# 07_FMC_LPC_Interface.net
KiCad netlist of a schematic drawn in Altium Designer
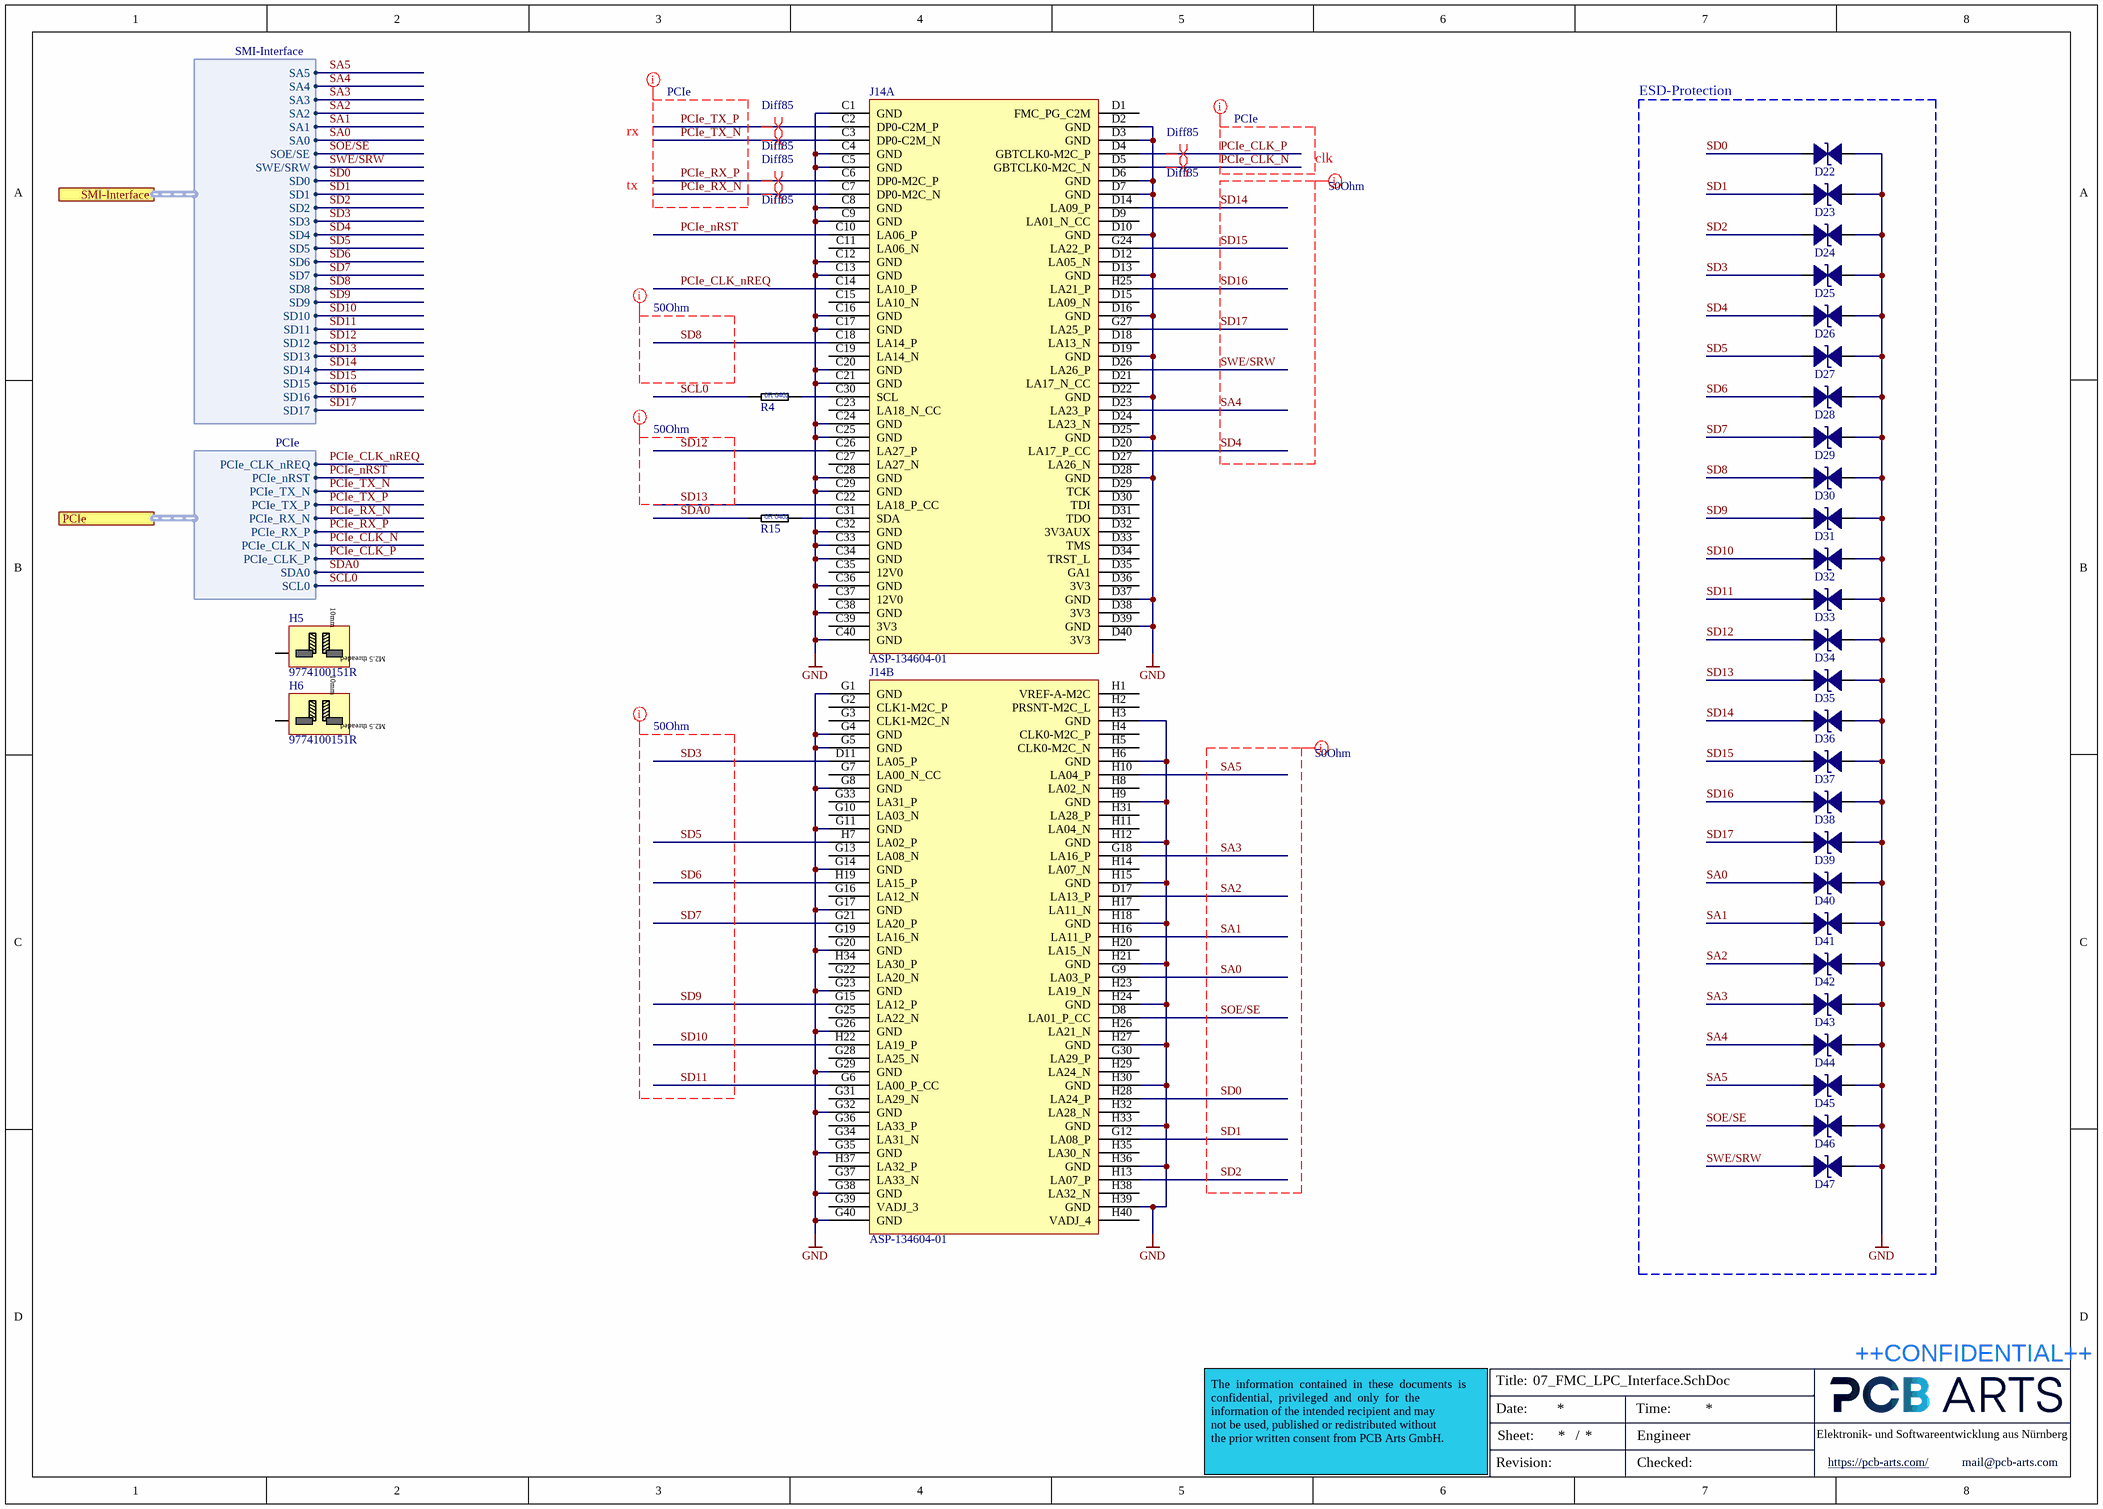
[diagram p0: 07_FMC_LPC_Interface.SchDoc]

(export (version "E")
  (design (tool "Eeschema 10.0.6"))
  (components
    (comp (ref "D22")
      (value "CESDP0402UC5VB")
      (footprint "Protec:TVS_0402")
      (description "Low Capacitance ESD Protection Diode 0402")
      (libsource (lib "Protec") (part "CESDP0402UC5VB_TVS Diode 0402"))
    )
    (comp (ref "D23")
      (value "CESDP0402UC5VB")
      (footprint "Protec:TVS_0402")
      (description "Low Capacitance ESD Protection Diode 0402")
      (libsource (lib "Protec") (part "CESDP0402UC5VB_TVS Diode 0402"))
    )
    (comp (ref "D24")
      (value "CESDP0402UC5VB")
      (footprint "Protec:TVS_0402")
      (description "Low Capacitance ESD Protection Diode 0402")
      (libsource (lib "Protec") (part "CESDP0402UC5VB_TVS Diode 0402"))
    )
    (comp (ref "D25")
      (value "CESDP0402UC5VB")
      (footprint "Protec:TVS_0402")
      (description "Low Capacitance ESD Protection Diode 0402")
      (libsource (lib "Protec") (part "CESDP0402UC5VB_TVS Diode 0402"))
    )
    (comp (ref "D26")
      (value "CESDP0402UC5VB")
      (footprint "Protec:TVS_0402")
      (description "Low Capacitance ESD Protection Diode 0402")
      (libsource (lib "Protec") (part "CESDP0402UC5VB_TVS Diode 0402"))
    )
    (comp (ref "D27")
      (value "CESDP0402UC5VB")
      (footprint "Protec:TVS_0402")
      (description "Low Capacitance ESD Protection Diode 0402")
      (libsource (lib "Protec") (part "CESDP0402UC5VB_TVS Diode 0402"))
    )
    (comp (ref "D28")
      (value "CESDP0402UC5VB")
      (footprint "Protec:TVS_0402")
      (description "Low Capacitance ESD Protection Diode 0402")
      (libsource (lib "Protec") (part "CESDP0402UC5VB_TVS Diode 0402"))
    )
    (comp (ref "D29")
      (value "CESDP0402UC5VB")
      (footprint "Protec:TVS_0402")
      (description "Low Capacitance ESD Protection Diode 0402")
      (libsource (lib "Protec") (part "CESDP0402UC5VB_TVS Diode 0402"))
    )
    (comp (ref "D30")
      (value "CESDP0402UC5VB")
      (footprint "Protec:TVS_0402")
      (description "Low Capacitance ESD Protection Diode 0402")
      (libsource (lib "Protec") (part "CESDP0402UC5VB_TVS Diode 0402"))
    )
    (comp (ref "D31")
      (value "CESDP0402UC5VB")
      (footprint "Protec:TVS_0402")
      (description "Low Capacitance ESD Protection Diode 0402")
      (libsource (lib "Protec") (part "CESDP0402UC5VB_TVS Diode 0402"))
    )
    (comp (ref "D32")
      (value "CESDP0402UC5VB")
      (footprint "Protec:TVS_0402")
      (description "Low Capacitance ESD Protection Diode 0402")
      (libsource (lib "Protec") (part "CESDP0402UC5VB_TVS Diode 0402"))
    )
    (comp (ref "D33")
      (value "CESDP0402UC5VB")
      (footprint "Protec:TVS_0402")
      (description "Low Capacitance ESD Protection Diode 0402")
      (libsource (lib "Protec") (part "CESDP0402UC5VB_TVS Diode 0402"))
    )
    (comp (ref "D34")
      (value "CESDP0402UC5VB")
      (footprint "Protec:TVS_0402")
      (description "Low Capacitance ESD Protection Diode 0402")
      (libsource (lib "Protec") (part "CESDP0402UC5VB_TVS Diode 0402"))
    )
    (comp (ref "D35")
      (value "CESDP0402UC5VB")
      (footprint "Protec:TVS_0402")
      (description "Low Capacitance ESD Protection Diode 0402")
      (libsource (lib "Protec") (part "CESDP0402UC5VB_TVS Diode 0402"))
    )
    (comp (ref "D36")
      (value "CESDP0402UC5VB")
      (footprint "Protec:TVS_0402")
      (description "Low Capacitance ESD Protection Diode 0402")
      (libsource (lib "Protec") (part "CESDP0402UC5VB_TVS Diode 0402"))
    )
    (comp (ref "D37")
      (value "CESDP0402UC5VB")
      (footprint "Protec:TVS_0402")
      (description "Low Capacitance ESD Protection Diode 0402")
      (libsource (lib "Protec") (part "CESDP0402UC5VB_TVS Diode 0402"))
    )
    (comp (ref "D38")
      (value "CESDP0402UC5VB")
      (footprint "Protec:TVS_0402")
      (description "Low Capacitance ESD Protection Diode 0402")
      (libsource (lib "Protec") (part "CESDP0402UC5VB_TVS Diode 0402"))
    )
    (comp (ref "D39")
      (value "CESDP0402UC5VB")
      (footprint "Protec:TVS_0402")
      (description "Low Capacitance ESD Protection Diode 0402")
      (libsource (lib "Protec") (part "CESDP0402UC5VB_TVS Diode 0402"))
    )
    (comp (ref "D40")
      (value "CESDP0402UC5VB")
      (footprint "Protec:TVS_0402")
      (description "Low Capacitance ESD Protection Diode 0402")
      (libsource (lib "Protec") (part "CESDP0402UC5VB_TVS Diode 0402"))
    )
    (comp (ref "D41")
      (value "CESDP0402UC5VB")
      (footprint "Protec:TVS_0402")
      (description "Low Capacitance ESD Protection Diode 0402")
      (libsource (lib "Protec") (part "CESDP0402UC5VB_TVS Diode 0402"))
    )
    (comp (ref "D42")
      (value "CESDP0402UC5VB")
      (footprint "Protec:TVS_0402")
      (description "Low Capacitance ESD Protection Diode 0402")
      (libsource (lib "Protec") (part "CESDP0402UC5VB_TVS Diode 0402"))
    )
    (comp (ref "D43")
      (value "CESDP0402UC5VB")
      (footprint "Protec:TVS_0402")
      (description "Low Capacitance ESD Protection Diode 0402")
      (libsource (lib "Protec") (part "CESDP0402UC5VB_TVS Diode 0402"))
    )
    (comp (ref "D44")
      (value "CESDP0402UC5VB")
      (footprint "Protec:TVS_0402")
      (description "Low Capacitance ESD Protection Diode 0402")
      (libsource (lib "Protec") (part "CESDP0402UC5VB_TVS Diode 0402"))
    )
    (comp (ref "D45")
      (value "CESDP0402UC5VB")
      (footprint "Protec:TVS_0402")
      (description "Low Capacitance ESD Protection Diode 0402")
      (libsource (lib "Protec") (part "CESDP0402UC5VB_TVS Diode 0402"))
    )
    (comp (ref "D46")
      (value "CESDP0402UC5VB")
      (footprint "Protec:TVS_0402")
      (description "Low Capacitance ESD Protection Diode 0402")
      (libsource (lib "Protec") (part "CESDP0402UC5VB_TVS Diode 0402"))
    )
    (comp (ref "D47")
      (value "CESDP0402UC5VB")
      (footprint "Protec:TVS_0402")
      (description "Low Capacitance ESD Protection Diode 0402")
      (libsource (lib "Protec") (part "CESDP0402UC5VB_TVS Diode 0402"))
    )
    (comp (ref "H5")
      (value "9774100151R")
      (footprint "Electro_Mech:9774100151R")
      (description "Würth Standoff M2.5 h:10mm 9774050151R")
      (libsource (lib "Electro_Mech") (part "Würth Standoff M2.5 h{colon}5mm_1"))
    )
    (comp (ref "H6")
      (value "9774100151R")
      (footprint "Electro_Mech:9774100151R")
      (description "Würth Standoff M2.5 h:10mm 9774050151R")
      (libsource (lib "Electro_Mech") (part "Würth Standoff M2.5 h{colon}5mm_1"))
    )
    (comp (ref "J14")
      (value "ASP-134604-01")
      (footprint "CONN:ASP-134604-01")
      (description "Female FMC-Connector mating plug")
      (libsource (lib "Conn") (part "ASP-134604-01_Female FMC-Connector mating plug"))
    )
    (comp (ref "R4")
      (value "0R Jumper")
      (footprint "res:RES_0402")
      (description "Thick Film Resistors - SMD 0Ohm")
      (libsource (lib "Res") (part "RES_0402_0R Jumper"))
    )
    (comp (ref "R15")
      (value "0R Jumper")
      (footprint "res:RES_0402")
      (description "Thick Film Resistors - SMD 0Ohm")
      (libsource (lib "Res") (part "RES_0402_0R Jumper"))
    )
  )
  (nets
    (net (code "3") (name "/PCIe_CLK_N") (class "Default")
      (node (ref "J14") (pin "D5") (pinfunction "GBTCLK0-M2C_N_D5") (pintype "passive"))
    )
    (net (code "4") (name "/PCIe_CLK_P") (class "Default")
      (node (ref "J14") (pin "D4") (pinfunction "GBTCLK0-M2C_P_D4") (pintype "passive"))
    )
    (net (code "5") (name "/PCIe_CLK_nREQ") (class "Default")
      (node (ref "J14") (pin "C14") (pinfunction "LA10_P_C14") (pintype "passive"))
    )
    (net (code "6") (name "/PCIe_RX_N") (class "Default")
      (node (ref "J14") (pin "C7") (pinfunction "DP0-M2C_N_C7") (pintype "passive"))
    )
    (net (code "7") (name "/PCIe_RX_P") (class "Default")
      (node (ref "J14") (pin "C6") (pinfunction "DP0-M2C_P_C6") (pintype "passive"))
    )
    (net (code "8") (name "/PCIe_TX_N") (class "Default")
      (node (ref "J14") (pin "C3") (pinfunction "DP0-C2M_N_C3") (pintype "passive"))
    )
    (net (code "9") (name "/PCIe_TX_P") (class "Default")
      (node (ref "J14") (pin "C2") (pinfunction "DP0-C2M_P_C2") (pintype "passive"))
    )
    (net (code "10") (name "/PCIe_nRST") (class "Default")
      (node (ref "J14") (pin "C10") (pinfunction "LA06_P_C10") (pintype "passive"))
    )
    (net (code "11") (name "/SA0") (class "Default")
      (node (ref "D40") (pin "1") (pinfunction "1_1") (pintype "passive"))
      (node (ref "J14") (pin "G9") (pinfunction "LA03_P_G9") (pintype "passive"))
    )
    (net (code "12") (name "/SA1") (class "Default")
      (node (ref "D41") (pin "1") (pinfunction "1_1") (pintype "passive"))
      (node (ref "J14") (pin "H16") (pinfunction "LA11_P_H16") (pintype "passive"))
    )
    (net (code "13") (name "/SA2") (class "Default")
      (node (ref "D42") (pin "1") (pinfunction "1_1") (pintype "passive"))
      (node (ref "J14") (pin "D17") (pinfunction "LA13_P_D17") (pintype "passive"))
    )
    (net (code "14") (name "/SA3") (class "Default")
      (node (ref "D43") (pin "1") (pinfunction "1_1") (pintype "passive"))
      (node (ref "J14") (pin "G18") (pinfunction "LA16_P_G18") (pintype "passive"))
    )
    (net (code "15") (name "/SA4") (class "Default")
      (node (ref "D44") (pin "1") (pinfunction "1_1") (pintype "passive"))
      (node (ref "J14") (pin "D23") (pinfunction "LA23_P_D23") (pintype "passive"))
    )
    (net (code "16") (name "/SA5") (class "Default")
      (node (ref "D45") (pin "1") (pinfunction "1_1") (pintype "passive"))
      (node (ref "J14") (pin "H10") (pinfunction "LA04_P_H10") (pintype "passive"))
    )
    (net (code "17") (name "/SCL0") (class "Default")
      (node (ref "R4") (pin "1") (pinfunction "1_1") (pintype "passive"))
    )
    (net (code "18") (name "/SD0") (class "Default")
      (node (ref "D22") (pin "1") (pinfunction "1_1") (pintype "passive"))
      (node (ref "J14") (pin "H28") (pinfunction "LA24_P_H28") (pintype "passive"))
    )
    (net (code "19") (name "/SD1") (class "Default")
      (node (ref "D23") (pin "1") (pinfunction "1_1") (pintype "passive"))
      (node (ref "J14") (pin "G12") (pinfunction "LA08_P_G12") (pintype "passive"))
    )
    (net (code "20") (name "/SD2") (class "Default")
      (node (ref "D24") (pin "1") (pinfunction "1_1") (pintype "passive"))
      (node (ref "J14") (pin "H13") (pinfunction "LA07_P_H13") (pintype "passive"))
    )
    (net (code "21") (name "/SD3") (class "Default")
      (node (ref "D25") (pin "1") (pinfunction "1_1") (pintype "passive"))
      (node (ref "J14") (pin "D11") (pinfunction "LA05_P_D11") (pintype "passive"))
    )
    (net (code "22") (name "/SD4") (class "Default")
      (node (ref "D26") (pin "1") (pinfunction "1_1") (pintype "passive"))
      (node (ref "J14") (pin "D20") (pinfunction "LA17_P_CC_D20") (pintype "passive"))
    )
    (net (code "23") (name "/SD5") (class "Default")
      (node (ref "D27") (pin "1") (pinfunction "1_1") (pintype "passive"))
      (node (ref "J14") (pin "H7") (pinfunction "LA02_P_H7") (pintype "passive"))
    )
    (net (code "24") (name "/SD6") (class "Default")
      (node (ref "D28") (pin "1") (pinfunction "1_1") (pintype "passive"))
      (node (ref "J14") (pin "H19") (pinfunction "LA15_P_H19") (pintype "passive"))
    )
    (net (code "25") (name "/SD7") (class "Default")
      (node (ref "D29") (pin "1") (pinfunction "1_1") (pintype "passive"))
      (node (ref "J14") (pin "G21") (pinfunction "LA20_P_G21") (pintype "passive"))
    )
    (net (code "26") (name "/SD8") (class "Default")
      (node (ref "D30") (pin "1") (pinfunction "1_1") (pintype "passive"))
      (node (ref "J14") (pin "C18") (pinfunction "LA14_P_C18") (pintype "passive"))
    )
    (net (code "27") (name "/SD9") (class "Default")
      (node (ref "D31") (pin "1") (pinfunction "1_1") (pintype "passive"))
      (node (ref "J14") (pin "G15") (pinfunction "LA12_P_G15") (pintype "passive"))
    )
    (net (code "28") (name "/SD10") (class "Default")
      (node (ref "D32") (pin "1") (pinfunction "1_1") (pintype "passive"))
      (node (ref "J14") (pin "H22") (pinfunction "LA19_P_H22") (pintype "passive"))
    )
    (net (code "29") (name "/SD11") (class "Default")
      (node (ref "D33") (pin "1") (pinfunction "1_1") (pintype "passive"))
      (node (ref "J14") (pin "G6") (pinfunction "LA00_P_CC_G6") (pintype "passive"))
    )
    (net (code "30") (name "/SD12") (class "Default")
      (node (ref "D34") (pin "1") (pinfunction "1_1") (pintype "passive"))
      (node (ref "J14") (pin "C26") (pinfunction "LA27_P_C26") (pintype "passive"))
    )
    (net (code "31") (name "/SD13") (class "Default")
      (node (ref "D35") (pin "1") (pinfunction "1_1") (pintype "passive"))
      (node (ref "J14") (pin "C22") (pinfunction "LA18_P_CC_C22") (pintype "passive"))
    )
    (net (code "32") (name "/SD14") (class "Default")
      (node (ref "D36") (pin "1") (pinfunction "1_1") (pintype "passive"))
      (node (ref "J14") (pin "D14") (pinfunction "LA09_P_D14") (pintype "passive"))
    )
    (net (code "33") (name "/SD15") (class "Default")
      (node (ref "D37") (pin "1") (pinfunction "1_1") (pintype "passive"))
      (node (ref "J14") (pin "G24") (pinfunction "LA22_P_G24") (pintype "passive"))
    )
    (net (code "34") (name "/SD16") (class "Default")
      (node (ref "D38") (pin "1") (pinfunction "1_1") (pintype "passive"))
      (node (ref "J14") (pin "H25") (pinfunction "LA21_P_H25") (pintype "passive"))
    )
    (net (code "35") (name "/SD17") (class "Default")
      (node (ref "D39") (pin "1") (pinfunction "1_1") (pintype "passive"))
      (node (ref "J14") (pin "G27") (pinfunction "LA25_P_G27") (pintype "passive"))
    )
    (net (code "36") (name "/SDA0") (class "Default")
      (node (ref "R15") (pin "1") (pinfunction "1_1") (pintype "passive"))
    )
    (net (code "37") (name "/SOE{slash}SE") (class "Default")
      (node (ref "D46") (pin "1") (pinfunction "1_1") (pintype "passive"))
      (node (ref "J14") (pin "D8") (pinfunction "LA01_P_CC_D8") (pintype "passive"))
    )
    (net (code "38") (name "/SWE{slash}SRW") (class "Default")
      (node (ref "D47") (pin "1") (pinfunction "1_1") (pintype "passive"))
      (node (ref "J14") (pin "D26") (pinfunction "LA26_P_D26") (pintype "passive"))
    )
    (net (code "41") (name "GND") (class "Default")
      (node (ref "D22") (pin "2") (pinfunction "2_2") (pintype "passive"))
      (node (ref "D23") (pin "2") (pinfunction "2_2") (pintype "passive"))
      (node (ref "D24") (pin "2") (pinfunction "2_2") (pintype "passive"))
      (node (ref "D25") (pin "2") (pinfunction "2_2") (pintype "passive"))
      (node (ref "D26") (pin "2") (pinfunction "2_2") (pintype "passive"))
      (node (ref "D27") (pin "2") (pinfunction "2_2") (pintype "passive"))
      (node (ref "D28") (pin "2") (pinfunction "2_2") (pintype "passive"))
      (node (ref "D29") (pin "2") (pinfunction "2_2") (pintype "passive"))
      (node (ref "D30") (pin "2") (pinfunction "2_2") (pintype "passive"))
      (node (ref "D31") (pin "2") (pinfunction "2_2") (pintype "passive"))
      (node (ref "D32") (pin "2") (pinfunction "2_2") (pintype "passive"))
      (node (ref "D33") (pin "2") (pinfunction "2_2") (pintype "passive"))
      (node (ref "D34") (pin "2") (pinfunction "2_2") (pintype "passive"))
      (node (ref "D35") (pin "2") (pinfunction "2_2") (pintype "passive"))
      (node (ref "D36") (pin "2") (pinfunction "2_2") (pintype "passive"))
      (node (ref "D37") (pin "2") (pinfunction "2_2") (pintype "passive"))
      (node (ref "D38") (pin "2") (pinfunction "2_2") (pintype "passive"))
      (node (ref "D39") (pin "2") (pinfunction "2_2") (pintype "passive"))
      (node (ref "D40") (pin "2") (pinfunction "2_2") (pintype "passive"))
      (node (ref "D41") (pin "2") (pinfunction "2_2") (pintype "passive"))
      (node (ref "D42") (pin "2") (pinfunction "2_2") (pintype "passive"))
      (node (ref "D43") (pin "2") (pinfunction "2_2") (pintype "passive"))
      (node (ref "D44") (pin "2") (pinfunction "2_2") (pintype "passive"))
      (node (ref "D45") (pin "2") (pinfunction "2_2") (pintype "passive"))
      (node (ref "D46") (pin "2") (pinfunction "2_2") (pintype "passive"))
      (node (ref "D47") (pin "2") (pinfunction "2_2") (pintype "passive"))
      (node (ref "J14") (pin "C1") (pinfunction "GND_C1") (pintype "passive"))
      (node (ref "J14") (pin "C12") (pinfunction "GND_C12") (pintype "passive"))
      (node (ref "J14") (pin "C13") (pinfunction "GND_C13") (pintype "passive"))
      (node (ref "J14") (pin "C16") (pinfunction "GND_C16") (pintype "passive"))
      (node (ref "J14") (pin "C17") (pinfunction "GND_C17") (pintype "passive"))
      (node (ref "J14") (pin "C20") (pinfunction "GND_C20") (pintype "passive"))
      (node (ref "J14") (pin "C21") (pinfunction "GND_C21") (pintype "passive"))
      (node (ref "J14") (pin "C24") (pinfunction "GND_C24") (pintype "passive"))
      (node (ref "J14") (pin "C25") (pinfunction "GND_C25") (pintype "passive"))
      (node (ref "J14") (pin "C28") (pinfunction "GND_C28") (pintype "passive"))
      (node (ref "J14") (pin "C29") (pinfunction "GND_C29") (pintype "passive"))
      (node (ref "J14") (pin "C32") (pinfunction "GND_C32") (pintype "passive"))
      (node (ref "J14") (pin "C33") (pinfunction "GND_C33") (pintype "passive"))
      (node (ref "J14") (pin "C34") (pinfunction "GND_C34") (pintype "passive"))
      (node (ref "J14") (pin "C36") (pinfunction "GND_C36") (pintype "passive"))
      (node (ref "J14") (pin "C38") (pinfunction "GND_C38") (pintype "passive"))
      (node (ref "J14") (pin "C4") (pinfunction "GND_C4") (pintype "passive"))
      (node (ref "J14") (pin "C40") (pinfunction "GND_C40") (pintype "passive"))
      (node (ref "J14") (pin "C5") (pinfunction "GND_C5") (pintype "passive"))
      (node (ref "J14") (pin "C8") (pinfunction "GND_C8") (pintype "passive"))
      (node (ref "J14") (pin "C9") (pinfunction "GND_C9") (pintype "passive"))
      (node (ref "J14") (pin "D10") (pinfunction "GND_D10") (pintype "passive"))
      (node (ref "J14") (pin "D13") (pinfunction "GND_D13") (pintype "passive"))
      (node (ref "J14") (pin "D16") (pinfunction "GND_D16") (pintype "passive"))
      (node (ref "J14") (pin "D19") (pinfunction "GND_D19") (pintype "passive"))
      (node (ref "J14") (pin "D2") (pinfunction "GND_D2") (pintype "passive"))
      (node (ref "J14") (pin "D22") (pinfunction "GND_D22") (pintype "passive"))
      (node (ref "J14") (pin "D25") (pinfunction "GND_D25") (pintype "passive"))
      (node (ref "J14") (pin "D28") (pinfunction "GND_D28") (pintype "passive"))
      (node (ref "J14") (pin "D3") (pinfunction "GND_D3") (pintype "passive"))
      (node (ref "J14") (pin "D37") (pinfunction "GND_D37") (pintype "passive"))
      (node (ref "J14") (pin "D39") (pinfunction "GND_D39") (pintype "passive"))
      (node (ref "J14") (pin "D6") (pinfunction "GND_D6") (pintype "passive"))
      (node (ref "J14") (pin "D7") (pinfunction "GND_D7") (pintype "passive"))
      (node (ref "J14") (pin "G1") (pinfunction "GND_G1") (pintype "passive"))
      (node (ref "J14") (pin "G11") (pinfunction "GND_G11") (pintype "passive"))
      (node (ref "J14") (pin "G14") (pinfunction "GND_G14") (pintype "passive"))
      (node (ref "J14") (pin "G17") (pinfunction "GND_G17") (pintype "passive"))
      (node (ref "J14") (pin "G20") (pinfunction "GND_G20") (pintype "passive"))
      (node (ref "J14") (pin "G23") (pinfunction "GND_G23") (pintype "passive"))
      (node (ref "J14") (pin "G26") (pinfunction "GND_G26") (pintype "passive"))
      (node (ref "J14") (pin "G29") (pinfunction "GND_G29") (pintype "passive"))
      (node (ref "J14") (pin "G32") (pinfunction "GND_G32") (pintype "passive"))
      (node (ref "J14") (pin "G35") (pinfunction "GND_G35") (pintype "passive"))
      (node (ref "J14") (pin "G38") (pinfunction "GND_G38") (pintype "passive"))
      (node (ref "J14") (pin "G4") (pinfunction "GND_G4") (pintype "passive"))
      (node (ref "J14") (pin "G40") (pinfunction "GND_G40") (pintype "passive"))
      (node (ref "J14") (pin "G5") (pinfunction "GND_G5") (pintype "passive"))
      (node (ref "J14") (pin "G8") (pinfunction "GND_G8") (pintype "passive"))
      (node (ref "J14") (pin "H12") (pinfunction "GND_H12") (pintype "passive"))
      (node (ref "J14") (pin "H15") (pinfunction "GND_H15") (pintype "passive"))
      (node (ref "J14") (pin "H18") (pinfunction "GND_H18") (pintype "passive"))
      (node (ref "J14") (pin "H21") (pinfunction "GND_H21") (pintype "passive"))
      (node (ref "J14") (pin "H24") (pinfunction "GND_H24") (pintype "passive"))
      (node (ref "J14") (pin "H27") (pinfunction "GND_H27") (pintype "passive"))
      (node (ref "J14") (pin "H3") (pinfunction "GND_H3") (pintype "passive"))
      (node (ref "J14") (pin "H30") (pinfunction "GND_H30") (pintype "passive"))
      (node (ref "J14") (pin "H33") (pinfunction "GND_H33") (pintype "passive"))
      (node (ref "J14") (pin "H36") (pinfunction "GND_H36") (pintype "passive"))
      (node (ref "J14") (pin "H39") (pinfunction "GND_H39") (pintype "passive"))
      (node (ref "J14") (pin "H6") (pinfunction "GND_H6") (pintype "passive"))
      (node (ref "J14") (pin "H9") (pinfunction "GND_H9") (pintype "passive"))
    )
    (net (code "42") (name "Net-(J14A-SCL)") (class "Default")
      (node (ref "J14") (pin "C30") (pinfunction "SCL_C30") (pintype "passive"))
      (node (ref "R4") (pin "2") (pinfunction "2_2") (pintype "passive"))
    )
    (net (code "43") (name "Net-(J14A-SDA)") (class "Default")
      (node (ref "J14") (pin "C31") (pinfunction "SDA_C31") (pintype "passive"))
      (node (ref "R15") (pin "2") (pinfunction "2_2") (pintype "passive"))
    )
    (net (code "44") (name "unconnected-(H5-Pad1)") (class "Default")
      (node (ref "H5") (pin "1") (pinfunction "1_1") (pintype "passive"))
    )
    (net (code "45") (name "unconnected-(H6-Pad1)") (class "Default")
      (node (ref "H6") (pin "1") (pinfunction "1_1") (pintype "passive"))
    )
    (net (code "46") (name "unconnected-(J14A-3V3-PadC39)") (class "Default")
      (node (ref "J14") (pin "C39") (pinfunction "3V3_C39") (pintype "passive"))
    )
    (net (code "47") (name "unconnected-(J14A-3V3-PadD36)") (class "Default")
      (node (ref "J14") (pin "D36") (pinfunction "3V3_D36") (pintype "passive"))
    )
    (net (code "48") (name "unconnected-(J14A-3V3-PadD38)") (class "Default")
      (node (ref "J14") (pin "D38") (pinfunction "3V3_D38") (pintype "passive"))
    )
    (net (code "49") (name "unconnected-(J14A-3V3-PadD40)") (class "Default")
      (node (ref "J14") (pin "D40") (pinfunction "3V3_D40") (pintype "passive"))
    )
    (net (code "50") (name "unconnected-(J14A-3V3AUX-PadD32)") (class "Default")
      (node (ref "J14") (pin "D32") (pinfunction "3V3AUX_D32") (pintype "passive"))
    )
    (net (code "51") (name "unconnected-(J14A-12V0-PadC35)") (class "Default")
      (node (ref "J14") (pin "C35") (pinfunction "12V0_C35") (pintype "passive"))
    )
    (net (code "52") (name "unconnected-(J14A-12V0-PadC37)") (class "Default")
      (node (ref "J14") (pin "C37") (pinfunction "12V0_C37") (pintype "passive"))
    )
    (net (code "53") (name "unconnected-(J14A-FMC_PG_C2M-PadD1)") (class "Default")
      (node (ref "J14") (pin "D1") (pinfunction "FMC_PG_C2M_D1") (pintype "passive"))
    )
    (net (code "54") (name "unconnected-(J14A-GA1-PadD35)") (class "Default")
      (node (ref "J14") (pin "D35") (pinfunction "GA1_D35") (pintype "passive"))
    )
    (net (code "55") (name "unconnected-(J14A-LA01_N_CC-PadD9)") (class "Default")
      (node (ref "J14") (pin "D9") (pinfunction "LA01_N_CC_D9") (pintype "passive"))
    )
    (net (code "56") (name "unconnected-(J14A-LA05_N-PadD12)") (class "Default")
      (node (ref "J14") (pin "D12") (pinfunction "LA05_N_D12") (pintype "passive"))
    )
    (net (code "57") (name "unconnected-(J14A-LA06_N-PadC11)") (class "Default")
      (node (ref "J14") (pin "C11") (pinfunction "LA06_N_C11") (pintype "passive"))
    )
    (net (code "58") (name "unconnected-(J14A-LA09_N-PadD15)") (class "Default")
      (node (ref "J14") (pin "D15") (pinfunction "LA09_N_D15") (pintype "passive"))
    )
    (net (code "59") (name "unconnected-(J14A-LA10_N-PadC15)") (class "Default")
      (node (ref "J14") (pin "C15") (pinfunction "LA10_N_C15") (pintype "passive"))
    )
    (net (code "60") (name "unconnected-(J14A-LA13_N-PadD18)") (class "Default")
      (node (ref "J14") (pin "D18") (pinfunction "LA13_N_D18") (pintype "passive"))
    )
    (net (code "61") (name "unconnected-(J14A-LA14_N-PadC19)") (class "Default")
      (node (ref "J14") (pin "C19") (pinfunction "LA14_N_C19") (pintype "passive"))
    )
    (net (code "62") (name "unconnected-(J14A-LA17_N_CC-PadD21)") (class "Default")
      (node (ref "J14") (pin "D21") (pinfunction "LA17_N_CC_D21") (pintype "passive"))
    )
    (net (code "63") (name "unconnected-(J14A-LA18_N_CC-PadC23)") (class "Default")
      (node (ref "J14") (pin "C23") (pinfunction "LA18_N_CC_C23") (pintype "passive"))
    )
    (net (code "64") (name "unconnected-(J14A-LA23_N-PadD24)") (class "Default")
      (node (ref "J14") (pin "D24") (pinfunction "LA23_N_D24") (pintype "passive"))
    )
    (net (code "65") (name "unconnected-(J14A-LA26_N-PadD27)") (class "Default")
      (node (ref "J14") (pin "D27") (pinfunction "LA26_N_D27") (pintype "passive"))
    )
    (net (code "66") (name "unconnected-(J14A-LA27_N-PadC27)") (class "Default")
      (node (ref "J14") (pin "C27") (pinfunction "LA27_N_C27") (pintype "passive"))
    )
    (net (code "67") (name "unconnected-(J14A-TCK-PadD29)") (class "Default")
      (node (ref "J14") (pin "D29") (pinfunction "TCK_D29") (pintype "passive"))
    )
    (net (code "68") (name "unconnected-(J14A-TDI-PadD30)") (class "Default")
      (node (ref "J14") (pin "D30") (pinfunction "TDI_D30") (pintype "passive"))
    )
    (net (code "69") (name "unconnected-(J14A-TDO-PadD31)") (class "Default")
      (node (ref "J14") (pin "D31") (pinfunction "TDO_D31") (pintype "passive"))
    )
    (net (code "70") (name "unconnected-(J14A-TMS-PadD33)") (class "Default")
      (node (ref "J14") (pin "D33") (pinfunction "TMS_D33") (pintype "passive"))
    )
    (net (code "71") (name "unconnected-(J14A-TRST_L-PadD34)") (class "Default")
      (node (ref "J14") (pin "D34") (pinfunction "TRST_L_D34") (pintype "passive"))
    )
    (net (code "72") (name "unconnected-(J14B-CLK0-M2C_N-PadH5)") (class "Default")
      (node (ref "J14") (pin "H5") (pinfunction "CLK0-M2C_N_H5") (pintype "passive"))
    )
    (net (code "73") (name "unconnected-(J14B-CLK0-M2C_P-PadH4)") (class "Default")
      (node (ref "J14") (pin "H4") (pinfunction "CLK0-M2C_P_H4") (pintype "passive"))
    )
    (net (code "74") (name "unconnected-(J14B-CLK1-M2C_N-PadG3)") (class "Default")
      (node (ref "J14") (pin "G3") (pinfunction "CLK1-M2C_N_G3") (pintype "passive"))
    )
    (net (code "75") (name "unconnected-(J14B-CLK1-M2C_P-PadG2)") (class "Default")
      (node (ref "J14") (pin "G2") (pinfunction "CLK1-M2C_P_G2") (pintype "passive"))
    )
    (net (code "76") (name "unconnected-(J14B-LA00_N_CC-PadG7)") (class "Default")
      (node (ref "J14") (pin "G7") (pinfunction "LA00_N_CC_G7") (pintype "passive"))
    )
    (net (code "77") (name "unconnected-(J14B-LA02_N-PadH8)") (class "Default")
      (node (ref "J14") (pin "H8") (pinfunction "LA02_N_H8") (pintype "passive"))
    )
    (net (code "78") (name "unconnected-(J14B-LA03_N-PadG10)") (class "Default")
      (node (ref "J14") (pin "G10") (pinfunction "LA03_N_G10") (pintype "passive"))
    )
    (net (code "79") (name "unconnected-(J14B-LA04_N-PadH11)") (class "Default")
      (node (ref "J14") (pin "H11") (pinfunction "LA04_N_H11") (pintype "passive"))
    )
    (net (code "80") (name "unconnected-(J14B-LA07_N-PadH14)") (class "Default")
      (node (ref "J14") (pin "H14") (pinfunction "LA07_N_H14") (pintype "passive"))
    )
    (net (code "81") (name "unconnected-(J14B-LA08_N-PadG13)") (class "Default")
      (node (ref "J14") (pin "G13") (pinfunction "LA08_N_G13") (pintype "passive"))
    )
    (net (code "82") (name "unconnected-(J14B-LA11_N-PadH17)") (class "Default")
      (node (ref "J14") (pin "H17") (pinfunction "LA11_N_H17") (pintype "passive"))
    )
    (net (code "83") (name "unconnected-(J14B-LA12_N-PadG16)") (class "Default")
      (node (ref "J14") (pin "G16") (pinfunction "LA12_N_G16") (pintype "passive"))
    )
    (net (code "84") (name "unconnected-(J14B-LA15_N-PadH20)") (class "Default")
      (node (ref "J14") (pin "H20") (pinfunction "LA15_N_H20") (pintype "passive"))
    )
    (net (code "85") (name "unconnected-(J14B-LA16_N-PadG19)") (class "Default")
      (node (ref "J14") (pin "G19") (pinfunction "LA16_N_G19") (pintype "passive"))
    )
    (net (code "86") (name "unconnected-(J14B-LA19_N-PadH23)") (class "Default")
      (node (ref "J14") (pin "H23") (pinfunction "LA19_N_H23") (pintype "passive"))
    )
    (net (code "87") (name "unconnected-(J14B-LA20_N-PadG22)") (class "Default")
      (node (ref "J14") (pin "G22") (pinfunction "LA20_N_G22") (pintype "passive"))
    )
    (net (code "88") (name "unconnected-(J14B-LA21_N-PadH26)") (class "Default")
      (node (ref "J14") (pin "H26") (pinfunction "LA21_N_H26") (pintype "passive"))
    )
    (net (code "89") (name "unconnected-(J14B-LA22_N-PadG25)") (class "Default")
      (node (ref "J14") (pin "G25") (pinfunction "LA22_N_G25") (pintype "passive"))
    )
    (net (code "90") (name "unconnected-(J14B-LA24_N-PadH29)") (class "Default")
      (node (ref "J14") (pin "H29") (pinfunction "LA24_N_H29") (pintype "passive"))
    )
    (net (code "91") (name "unconnected-(J14B-LA25_N-PadG28)") (class "Default")
      (node (ref "J14") (pin "G28") (pinfunction "LA25_N_G28") (pintype "passive"))
    )
    (net (code "92") (name "unconnected-(J14B-LA28_N-PadH32)") (class "Default")
      (node (ref "J14") (pin "H32") (pinfunction "LA28_N_H32") (pintype "passive"))
    )
    (net (code "93") (name "unconnected-(J14B-LA28_P-PadH31)") (class "Default")
      (node (ref "J14") (pin "H31") (pinfunction "LA28_P_H31") (pintype "passive"))
    )
    (net (code "94") (name "unconnected-(J14B-LA29_N-PadG31)") (class "Default")
      (node (ref "J14") (pin "G31") (pinfunction "LA29_N_G31") (pintype "passive"))
    )
    (net (code "95") (name "unconnected-(J14B-LA29_P-PadG30)") (class "Default")
      (node (ref "J14") (pin "G30") (pinfunction "LA29_P_G30") (pintype "passive"))
    )
    (net (code "96") (name "unconnected-(J14B-LA30_N-PadH35)") (class "Default")
      (node (ref "J14") (pin "H35") (pinfunction "LA30_N_H35") (pintype "passive"))
    )
    (net (code "97") (name "unconnected-(J14B-LA30_P-PadH34)") (class "Default")
      (node (ref "J14") (pin "H34") (pinfunction "LA30_P_H34") (pintype "passive"))
    )
    (net (code "98") (name "unconnected-(J14B-LA31_N-PadG34)") (class "Default")
      (node (ref "J14") (pin "G34") (pinfunction "LA31_N_G34") (pintype "passive"))
    )
    (net (code "99") (name "unconnected-(J14B-LA31_P-PadG33)") (class "Default")
      (node (ref "J14") (pin "G33") (pinfunction "LA31_P_G33") (pintype "passive"))
    )
    (net (code "100") (name "unconnected-(J14B-LA32_N-PadH38)") (class "Default")
      (node (ref "J14") (pin "H38") (pinfunction "LA32_N_H38") (pintype "passive"))
    )
    (net (code "101") (name "unconnected-(J14B-LA32_P-PadH37)") (class "Default")
      (node (ref "J14") (pin "H37") (pinfunction "LA32_P_H37") (pintype "passive"))
    )
    (net (code "102") (name "unconnected-(J14B-LA33_N-PadG37)") (class "Default")
      (node (ref "J14") (pin "G37") (pinfunction "LA33_N_G37") (pintype "passive"))
    )
    (net (code "103") (name "unconnected-(J14B-LA33_P-PadG36)") (class "Default")
      (node (ref "J14") (pin "G36") (pinfunction "LA33_P_G36") (pintype "passive"))
    )
    (net (code "104") (name "unconnected-(J14B-PRSNT-M2C_L-PadH2)") (class "Default")
      (node (ref "J14") (pin "H2") (pinfunction "PRSNT-M2C_L_H2") (pintype "passive"))
    )
    (net (code "105") (name "unconnected-(J14B-VADJ_3-PadG39)") (class "Default")
      (node (ref "J14") (pin "G39") (pinfunction "VADJ_3_G39") (pintype "passive"))
    )
    (net (code "106") (name "unconnected-(J14B-VADJ_4-PadH40)") (class "Default")
      (node (ref "J14") (pin "H40") (pinfunction "VADJ_4_H40") (pintype "passive"))
    )
    (net (code "107") (name "unconnected-(J14B-VREF-A-M2C-PadH1)") (class "Default")
      (node (ref "J14") (pin "H1") (pinfunction "VREF-A-M2C_H1") (pintype "passive"))
    )
  )
)
